# Interfaz_Motor_Maxon.net
KiCad netlist of a schematic drawn in EAGLE
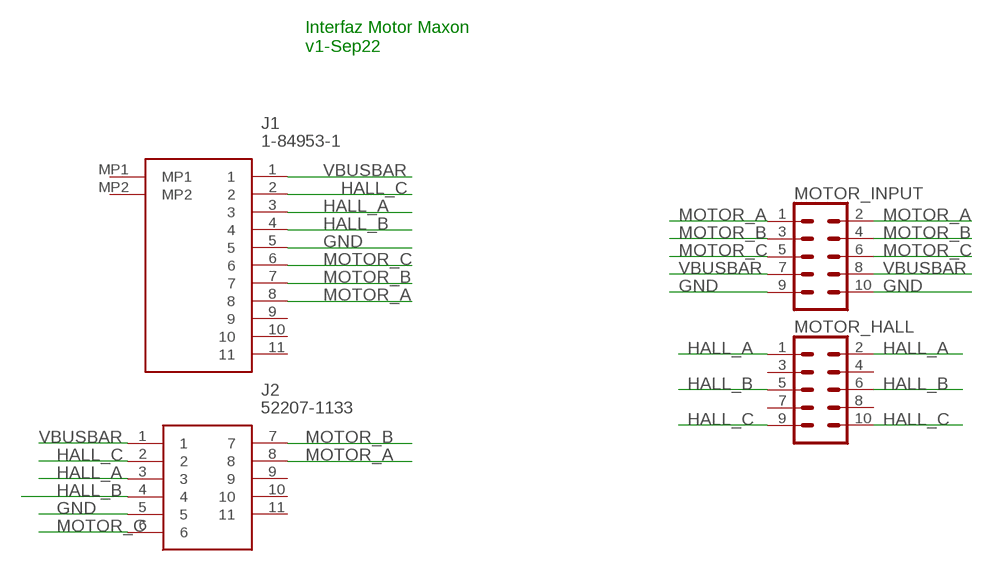
[diagram p0: schematic, sheet 1]

(export (version "E")
  (design (tool "Eeschema 10.0.6"))
  (components
    (comp (ref "J1")
      (value "1-84953-1")
      (footprint "eagle-import:1849531")
      (fields (field (name "MOUSER_PART_NUMBER") "571-1-84953-1"))
      (libsource (lib "eagle-import") (part "1-84953-1"))
    )
    (comp (ref "J2")
      (value "52207-1133")
      (footprint "eagle-import:52207-1133")
      (fields (field (name "MOUSER_PART_NUMBER") "538-52207-1133"))
      (libsource (lib "eagle-import") (part "52207-1133"))
    )
    (comp (ref "MOTOR_HALL")
      (value "CONN_05X2PTH")
      (footprint "eagle-import:2X5")
      (libsource (lib "eagle-import") (part "CONN_05X2PTH"))
    )
    (comp (ref "MOTOR_INPUT")
      (value "CONN_05X2PTH")
      (footprint "eagle-import:2X5")
      (libsource (lib "eagle-import") (part "CONN_05X2PTH"))
    )
  )
  (nets
    (net (code "1") (name "/GND") (class "Default")
      (node (ref "J1") (pin "5") (pinfunction "5_5") (pintype "bidirectional"))
      (node (ref "J2") (pin "5") (pinfunction "5_5") (pintype "bidirectional"))
      (node (ref "MOTOR_INPUT") (pin "10") (pinfunction "10_10") (pintype "passive"))
      (node (ref "MOTOR_INPUT") (pin "9") (pinfunction "9_9") (pintype "passive"))
    )
    (net (code "2") (name "/HALL_A") (class "Default")
      (node (ref "J1") (pin "3") (pinfunction "3_3") (pintype "bidirectional"))
      (node (ref "J2") (pin "3") (pinfunction "3_3") (pintype "bidirectional"))
      (node (ref "MOTOR_HALL") (pin "1") (pinfunction "1_1") (pintype "passive"))
      (node (ref "MOTOR_HALL") (pin "2") (pinfunction "2_2") (pintype "passive"))
    )
    (net (code "3") (name "/HALL_B") (class "Default")
      (node (ref "J1") (pin "4") (pinfunction "4_4") (pintype "bidirectional"))
      (node (ref "J2") (pin "4") (pinfunction "4_4") (pintype "bidirectional"))
      (node (ref "MOTOR_HALL") (pin "5") (pinfunction "5_5") (pintype "passive"))
      (node (ref "MOTOR_HALL") (pin "6") (pinfunction "6_6") (pintype "passive"))
    )
    (net (code "4") (name "/HALL_C") (class "Default")
      (node (ref "J1") (pin "2") (pinfunction "2_2") (pintype "bidirectional"))
      (node (ref "J2") (pin "2") (pinfunction "2_2") (pintype "bidirectional"))
      (node (ref "MOTOR_HALL") (pin "10") (pinfunction "10_10") (pintype "passive"))
      (node (ref "MOTOR_HALL") (pin "9") (pinfunction "9_9") (pintype "passive"))
    )
    (net (code "5") (name "/MOTOR_A") (class "Default")
      (node (ref "J1") (pin "8") (pinfunction "8_8") (pintype "bidirectional"))
      (node (ref "J2") (pin "8") (pinfunction "8_8") (pintype "bidirectional"))
      (node (ref "MOTOR_INPUT") (pin "1") (pinfunction "1_1") (pintype "passive"))
      (node (ref "MOTOR_INPUT") (pin "2") (pinfunction "2_2") (pintype "passive"))
    )
    (net (code "6") (name "/MOTOR_B") (class "Default")
      (node (ref "J1") (pin "7") (pinfunction "7_7") (pintype "bidirectional"))
      (node (ref "J2") (pin "7") (pinfunction "7_7") (pintype "bidirectional"))
      (node (ref "MOTOR_INPUT") (pin "3") (pinfunction "3_3") (pintype "passive"))
      (node (ref "MOTOR_INPUT") (pin "4") (pinfunction "4_4") (pintype "passive"))
    )
    (net (code "7") (name "/MOTOR_C") (class "Default")
      (node (ref "J1") (pin "6") (pinfunction "6_6") (pintype "bidirectional"))
      (node (ref "J2") (pin "6") (pinfunction "6_6") (pintype "bidirectional"))
      (node (ref "MOTOR_INPUT") (pin "5") (pinfunction "5_5") (pintype "passive"))
      (node (ref "MOTOR_INPUT") (pin "6") (pinfunction "6_6") (pintype "passive"))
    )
    (net (code "8") (name "/VBUSBAR") (class "Default")
      (node (ref "J1") (pin "1") (pinfunction "1_1") (pintype "bidirectional"))
      (node (ref "J2") (pin "1") (pinfunction "1_1") (pintype "bidirectional"))
      (node (ref "MOTOR_INPUT") (pin "7") (pinfunction "7_7") (pintype "passive"))
      (node (ref "MOTOR_INPUT") (pin "8") (pinfunction "8_8") (pintype "passive"))
    )
    (net (code "9") (name "unconnected-(J1-Pad9)") (class "Default")
      (node (ref "J1") (pin "9") (pinfunction "9_9") (pintype "bidirectional"))
    )
    (net (code "10") (name "unconnected-(J1-Pad10)") (class "Default")
      (node (ref "J1") (pin "10") (pinfunction "10_10") (pintype "bidirectional"))
    )
    (net (code "11") (name "unconnected-(J1-Pad11)") (class "Default")
      (node (ref "J1") (pin "11") (pinfunction "11_11") (pintype "bidirectional"))
    )
    (net (code "12") (name "unconnected-(J1-PadMP1)") (class "Default")
      (node (ref "J1") (pin "MP1") (pinfunction "MP1_MP1") (pintype "bidirectional"))
    )
    (net (code "13") (name "unconnected-(J1-PadMP2)") (class "Default")
      (node (ref "J1") (pin "MP2") (pinfunction "MP2_MP2") (pintype "bidirectional"))
    )
    (net (code "14") (name "unconnected-(J2-Pad9)") (class "Default")
      (node (ref "J2") (pin "9") (pinfunction "9_9") (pintype "bidirectional"))
    )
    (net (code "15") (name "unconnected-(J2-Pad10)") (class "Default")
      (node (ref "J2") (pin "10") (pinfunction "10_10") (pintype "bidirectional"))
    )
    (net (code "16") (name "unconnected-(J2-Pad11)") (class "Default")
      (node (ref "J2") (pin "11") (pinfunction "11_11") (pintype "bidirectional"))
    )
    (net (code "17") (name "unconnected-(MOTOR_HALL-Pad3)") (class "Default")
      (node (ref "MOTOR_HALL") (pin "3") (pinfunction "3_3") (pintype "passive"))
    )
    (net (code "18") (name "unconnected-(MOTOR_HALL-Pad4)") (class "Default")
      (node (ref "MOTOR_HALL") (pin "4") (pinfunction "4_4") (pintype "passive"))
    )
    (net (code "19") (name "unconnected-(MOTOR_HALL-Pad7)") (class "Default")
      (node (ref "MOTOR_HALL") (pin "7") (pinfunction "7_7") (pintype "passive"))
    )
    (net (code "20") (name "unconnected-(MOTOR_HALL-Pad8)") (class "Default")
      (node (ref "MOTOR_HALL") (pin "8") (pinfunction "8_8") (pintype "passive"))
    )
  )
)
